# eta2858_evb.net
KiCad netlist of a schematic drawn in Altium Designer
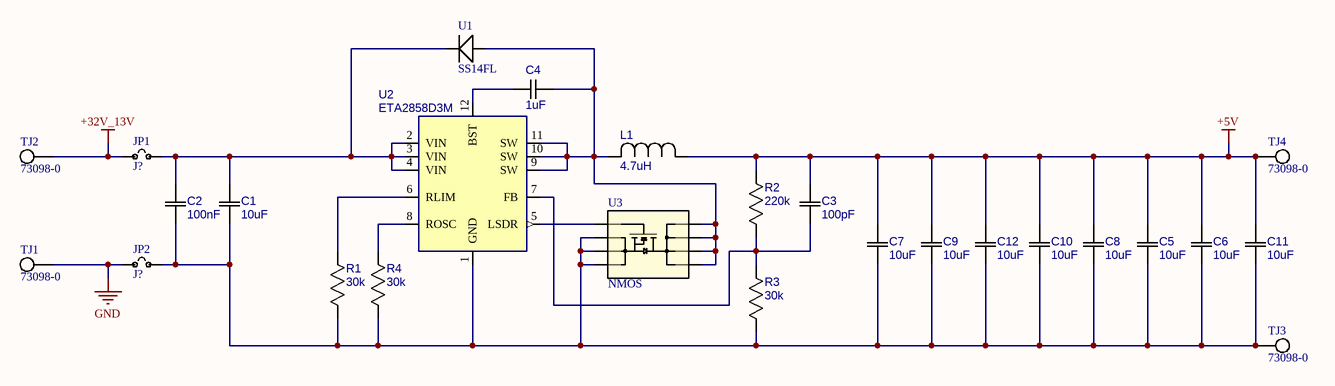
[diagram p0: eta2858_evb.SchDoc]

(export (version "E")
  (design (tool "Eeschema 10.0.6"))
  (components
    (comp (ref "C1")
      (value "10uF")
      (footprint "CAP_CL31_SAM")
      (description "CL31B106KBHNNNE\r\nMultilayer Ceramic Capacitors MLCC - SMD/SMT 10uF+/-10% 50V X7R 3 1206")
      (fields (field (name "MFR.") "Samsung Electro-Mechanics"))
      (libsource (lib "CL31B475KBHNNNE") (part "CL31B106KBHNNNE"))
    )
    (comp (ref "C2")
      (value "100nF")
      (footprint "CAP_CC0402_YAG")
      (description "GCM155R71H104ME02J\r\nMultilayer Ceramic Capacitors MLCC - SMD/SMT")
      (fields (field (name "MFR.") "Murata Electronics"))
      (libsource (lib "CC0402MRX5R6BB106") (part "GCM155R71H104ME02J"))
    )
    (comp (ref "C3")
      (value "100pF")
      (footprint "CAP_CC0402_YAG")
      (description "GCM1555C1H101JA16D\r\nMultilayer Ceramic Capacitors MLCC - SMD/SMT 100PF 50V 5% 0402")
      (fields (field (name "MFR.") "Murata Electronics"))
      (libsource (lib "CC0402MRX5R6BB106") (part "GCM1555C1H101JA16D"))
    )
    (comp (ref "C4")
      (value "1uF")
      (footprint "*CAPC1608X90")
      (description "1uF(105) ±20% 50V X7R 0603F105M500NT")
      (fields (field (name "MP") "C0603C104Z3VACTU") (field (name "MF") "KEMET"))
      (libsource (lib "C0603C104Z3VACTU") (part "0603F105M500NT"))
    )
    (comp (ref "C5")
      (value "10uF")
      (footprint "CAP_CL31_SAM")
      (description "CL31B106KBHNNNE\r\nMultilayer Ceramic Capacitors MLCC - SMD/SMT 10uF+/-10% 50V X7R 3 1206")
      (fields (field (name "MFR.") "Samsung Electro-Mechanics"))
      (libsource (lib "CL31B475KBHNNNE") (part "CL31B106KBHNNNE"))
    )
    (comp (ref "C6")
      (value "10uF")
      (footprint "CAP_CL31_SAM")
      (description "CL31B106KBHNNNE\r\nMultilayer Ceramic Capacitors MLCC - SMD/SMT 10uF+/-10% 50V X7R 3 1206")
      (fields (field (name "MFR.") "Samsung Electro-Mechanics"))
      (libsource (lib "CL31B475KBHNNNE") (part "CL31B106KBHNNNE"))
    )
    (comp (ref "C7")
      (value "10uF")
      (footprint "CAP_CL31_SAM")
      (description "CL31B106KBHNNNE\r\nMultilayer Ceramic Capacitors MLCC - SMD/SMT 10uF+/-10% 50V X7R 3 1206")
      (fields (field (name "MFR.") "Samsung Electro-Mechanics"))
      (libsource (lib "CL31B475KBHNNNE") (part "CL31B106KBHNNNE"))
    )
    (comp (ref "C8")
      (value "10uF")
      (footprint "CAP_CL31_SAM")
      (description "CL31B106KBHNNNE\r\nMultilayer Ceramic Capacitors MLCC - SMD/SMT 10uF+/-10% 50V X7R 3 1206")
      (fields (field (name "MFR.") "Samsung Electro-Mechanics"))
      (libsource (lib "CL31B475KBHNNNE") (part "CL31B106KBHNNNE"))
    )
    (comp (ref "C9")
      (value "10uF")
      (footprint "CAP_CL31_SAM")
      (description "CL31B106KBHNNNE\r\nMultilayer Ceramic Capacitors MLCC - SMD/SMT 10uF+/-10% 50V X7R 3 1206")
      (fields (field (name "MFR.") "Samsung Electro-Mechanics"))
      (libsource (lib "CL31B475KBHNNNE") (part "CL31B106KBHNNNE"))
    )
    (comp (ref "C10")
      (value "10uF")
      (footprint "CAP_CL31_SAM")
      (description "CL31B106KBHNNNE\r\nMultilayer Ceramic Capacitors MLCC - SMD/SMT 10uF+/-10% 50V X7R 3 1206")
      (fields (field (name "MFR.") "Samsung Electro-Mechanics"))
      (libsource (lib "CL31B475KBHNNNE") (part "CL31B106KBHNNNE"))
    )
    (comp (ref "C11")
      (value "10uF")
      (footprint "CAP_CL31_SAM")
      (description "CL31B106KBHNNNE\r\nMultilayer Ceramic Capacitors MLCC - SMD/SMT 10uF+/-10% 50V X7R 3 1206")
      (fields (field (name "MFR.") "Samsung Electro-Mechanics"))
      (libsource (lib "CL31B475KBHNNNE") (part "CL31B106KBHNNNE"))
    )
    (comp (ref "C12")
      (value "10uF")
      (footprint "CAP_CL31_SAM")
      (description "CL31B106KBHNNNE\r\nMultilayer Ceramic Capacitors MLCC - SMD/SMT 10uF+/-10% 50V X7R 3 1206")
      (fields (field (name "MFR.") "Samsung Electro-Mechanics"))
      (libsource (lib "CL31B475KBHNNNE") (part "CL31B106KBHNNNE"))
    )
    (comp (ref "JP1") (value "J?") (footprint "JP") (libsource (lib "jump_s0") (part "J")))
    (comp (ref "JP2") (value "J?") (footprint "JP") (libsource (lib "jump_s0") (part "J")))
    (comp (ref "L1")
      (value "4.7uH")
      (footprint "IND_SRP1040VA-1R5M_BRN")
      (description "SRP1040VA-1R5M")
      (libsource (lib "SRP1040VA-1R5M") (part "SRP1040VA-1R5M"))
    )
    (comp (ref "R1")
      (value "30k")
      (footprint "0402_PAN")
      (description "RT0402FRE0730KL\r\nThin Film Resistors - SMD 1/16W 30K ohm 1% 50ppm")
      (fields (field (name "MFR.") "YAGEO"))
      (libsource (lib "R0402") (part "RT0402FRE0730KL"))
    )
    (comp (ref "R2")
      (value "220k")
      (footprint "0402_PAN")
      (description "RT0402FRE07220KL\r\nThin Film Resistors - SMD 220K ohm 1% 50ppm High Stability")
      (fields (field (name "MFR.") "YAGEO"))
      (libsource (lib "R0402") (part "RT0402FRE07220KL"))
    )
    (comp (ref "R3")
      (value "30k")
      (footprint "0402_PAN")
      (description "RT0402FRE0730KL\r\nThin Film Resistors - SMD 1/16W 30K ohm 1% 50ppm")
      (fields (field (name "MFR.") "YAGEO"))
      (libsource (lib "R0402") (part "RT0402FRE0730KL"))
    )
    (comp (ref "R4")
      (value "30k")
      (footprint "0402_PAN")
      (description "RT0402FRE0730KL\r\nThin Film Resistors - SMD 1/16W 30K ohm 1% 50ppm")
      (fields (field (name "MFR.") "YAGEO"))
      (libsource (lib "R0402") (part "RT0402FRE0730KL"))
    )
    (comp (ref "TJ1")
      (value "73098-0")
      (footprint "73098")
      (fields (field (name "MANUFACTURER") "Pomona Electronics"))
      (libsource (lib "73098-0") (part "73098-0"))
    )
    (comp (ref "TJ2")
      (value "73098-0")
      (footprint "73098")
      (fields (field (name "MANUFACTURER") "Pomona Electronics"))
      (libsource (lib "73098-0") (part "73098-0"))
    )
    (comp (ref "TJ3")
      (value "73098-0")
      (footprint "73098")
      (fields (field (name "MANUFACTURER") "Pomona Electronics"))
      (libsource (lib "73098-0") (part "73098-0"))
    )
    (comp (ref "TJ4")
      (value "73098-0")
      (footprint "73098")
      (fields (field (name "MANUFACTURER") "Pomona Electronics"))
      (libsource (lib "73098-0") (part "73098-0"))
    )
    (comp (ref "U1")
      (value "SS14FL")
      (footprint "SOD-123_ONS")
      (fields (field (name "COPYRIGHT") "Copyright (C) 2022 Ultra Librarian. All rights reserved."))
      (libsource (lib "SS14FL") (part "SS14FL"))
    )
    (comp (ref "U2")
      (value "ETA2858D3M")
      (footprint "DFN3x3-12")
      (libsource (lib "eta-semi") (part "ETA2858D3M"))
    )
    (comp (ref "U3")
      (value "NMOS")
      (footprint "SMT_009LCG-7_DIO")
      (description "DMT10H009LCG-7")
      (fields (field (name "COPYRIGHT") "Copyright (C) 2022 Ultra Librarian. All rights reserved."))
      (libsource (lib "DMT10H009LCG-7") (part "DMT10H009LCG-7"))
    )
  )
  (nets
    (net (code "1") (name "+5V") (class "Default")
      (node (ref "C10") (pin "2") (pinfunction "2_2") (pintype "passive"))
      (node (ref "C11") (pin "2") (pinfunction "2_2") (pintype "passive"))
      (node (ref "C12") (pin "2") (pinfunction "2_2") (pintype "passive"))
      (node (ref "C3") (pin "2") (pinfunction "2_2") (pintype "passive"))
      (node (ref "C5") (pin "2") (pinfunction "2_2") (pintype "passive"))
      (node (ref "C6") (pin "2") (pinfunction "2_2") (pintype "passive"))
      (node (ref "C7") (pin "2") (pinfunction "2_2") (pintype "passive"))
      (node (ref "C8") (pin "2") (pinfunction "2_2") (pintype "passive"))
      (node (ref "C9") (pin "2") (pinfunction "2_2") (pintype "passive"))
      (node (ref "L1") (pin "1") (pinfunction "1_1") (pintype "passive"))
      (node (ref "R2") (pin "2") (pinfunction "2_2") (pintype "passive"))
      (node (ref "TJ4") (pin "T1") (pinfunction "T1_T1") (pintype "passive"))
    )
    (net (code "2") (name "+32V_13V") (class "Default")
      (node (ref "JP1") (pin "1") (pinfunction "PIN_1") (pintype "passive"))
      (node (ref "TJ2") (pin "T1") (pinfunction "T1_T1") (pintype "passive"))
    )
    (net (code "3") (name "GND") (class "Default")
      (node (ref "JP2") (pin "1") (pinfunction "PIN_1") (pintype "passive"))
      (node (ref "TJ1") (pin "T1") (pinfunction "T1_T1") (pintype "passive"))
    )
    (net (code "4") (name "Net-(U1-ANODE)") (class "Default")
      (node (ref "C4") (pin "1") (pinfunction "1_1") (pintype "passive"))
      (node (ref "L1") (pin "2") (pinfunction "2_2") (pintype "passive"))
      (node (ref "U1") (pin "2") (pinfunction "ANODE_2") (pintype "passive"))
      (node (ref "U2") (pin "10") (pinfunction "SW_10") (pintype "power_in"))
      (node (ref "U2") (pin "11") (pinfunction "SW_11") (pintype "power_in"))
      (node (ref "U2") (pin "9") (pinfunction "SW_9") (pintype "power_in"))
      (node (ref "U3") (pin "5") (pinfunction "5_5") (pintype "passive"))
      (node (ref "U3") (pin "6") (pinfunction "6_6") (pintype "passive"))
      (node (ref "U3") (pin "7") (pinfunction "7_7") (pintype "passive"))
      (node (ref "U3") (pin "8") (pinfunction "8_8") (pintype "passive"))
    )
    (net (code "5") (name "Net-(U1-CATHODE)") (class "Default")
      (node (ref "C1") (pin "2") (pinfunction "2_2") (pintype "passive"))
      (node (ref "C2") (pin "2") (pinfunction "2_2") (pintype "passive"))
      (node (ref "JP1") (pin "2") (pinfunction "PIN_2") (pintype "passive"))
      (node (ref "U1") (pin "1") (pinfunction "CATHODE_1") (pintype "passive"))
      (node (ref "U2") (pin "2") (pinfunction "VIN_2") (pintype "power_in"))
      (node (ref "U2") (pin "3") (pinfunction "VIN_3") (pintype "power_in"))
      (node (ref "U2") (pin "4") (pinfunction "VIN_4") (pintype "power_in"))
    )
    (net (code "6") (name "Net-(U2-BST)") (class "Default")
      (node (ref "C4") (pin "2") (pinfunction "2_2") (pintype "passive"))
      (node (ref "U2") (pin "12") (pinfunction "BST_12") (pintype "power_in"))
    )
    (net (code "7") (name "Net-(U2-FB)") (class "Default")
      (node (ref "C3") (pin "1") (pinfunction "1_1") (pintype "passive"))
      (node (ref "R2") (pin "1") (pinfunction "1_1") (pintype "passive"))
      (node (ref "R3") (pin "2") (pinfunction "2_2") (pintype "passive"))
      (node (ref "U2") (pin "7") (pinfunction "FB_7") (pintype "passive"))
    )
    (net (code "8") (name "Net-(U2-GND)") (class "Default")
      (node (ref "C1") (pin "1") (pinfunction "1_1") (pintype "passive"))
      (node (ref "C10") (pin "1") (pinfunction "1_1") (pintype "passive"))
      (node (ref "C11") (pin "1") (pinfunction "1_1") (pintype "passive"))
      (node (ref "C12") (pin "1") (pinfunction "1_1") (pintype "passive"))
      (node (ref "C2") (pin "1") (pinfunction "1_1") (pintype "passive"))
      (node (ref "C5") (pin "1") (pinfunction "1_1") (pintype "passive"))
      (node (ref "C6") (pin "1") (pinfunction "1_1") (pintype "passive"))
      (node (ref "C7") (pin "1") (pinfunction "1_1") (pintype "passive"))
      (node (ref "C8") (pin "1") (pinfunction "1_1") (pintype "passive"))
      (node (ref "C9") (pin "1") (pinfunction "1_1") (pintype "passive"))
      (node (ref "JP2") (pin "2") (pinfunction "PIN_2") (pintype "passive"))
      (node (ref "R1") (pin "1") (pinfunction "1_1") (pintype "passive"))
      (node (ref "R3") (pin "1") (pinfunction "1_1") (pintype "passive"))
      (node (ref "R4") (pin "1") (pinfunction "1_1") (pintype "passive"))
      (node (ref "TJ3") (pin "T1") (pinfunction "T1_T1") (pintype "passive"))
      (node (ref "U2") (pin "1") (pinfunction "GND_1") (pintype "power_in"))
      (node (ref "U3") (pin "1") (pinfunction "1_1") (pintype "passive"))
      (node (ref "U3") (pin "2") (pinfunction "2_2") (pintype "passive"))
      (node (ref "U3") (pin "3") (pinfunction "3_3") (pintype "passive"))
    )
    (net (code "9") (name "Net-(U2-LSDR)") (class "Default")
      (node (ref "U2") (pin "5") (pinfunction "LSDR_5") (pintype "output"))
      (node (ref "U3") (pin "4") (pinfunction "4_4") (pintype "passive"))
    )
    (net (code "10") (name "Net-(U2-RLIM)") (class "Default")
      (node (ref "R1") (pin "2") (pinfunction "2_2") (pintype "passive"))
      (node (ref "U2") (pin "6") (pinfunction "RLIM_6") (pintype "passive"))
    )
    (net (code "11") (name "Net-(U2-ROSC)") (class "Default")
      (node (ref "R4") (pin "2") (pinfunction "2_2") (pintype "passive"))
      (node (ref "U2") (pin "8") (pinfunction "ROSC_8") (pintype "passive"))
    )
  )
)
